# temperature-shift-r1.net
KiCad netlist of a schematic drawn in EAGLE
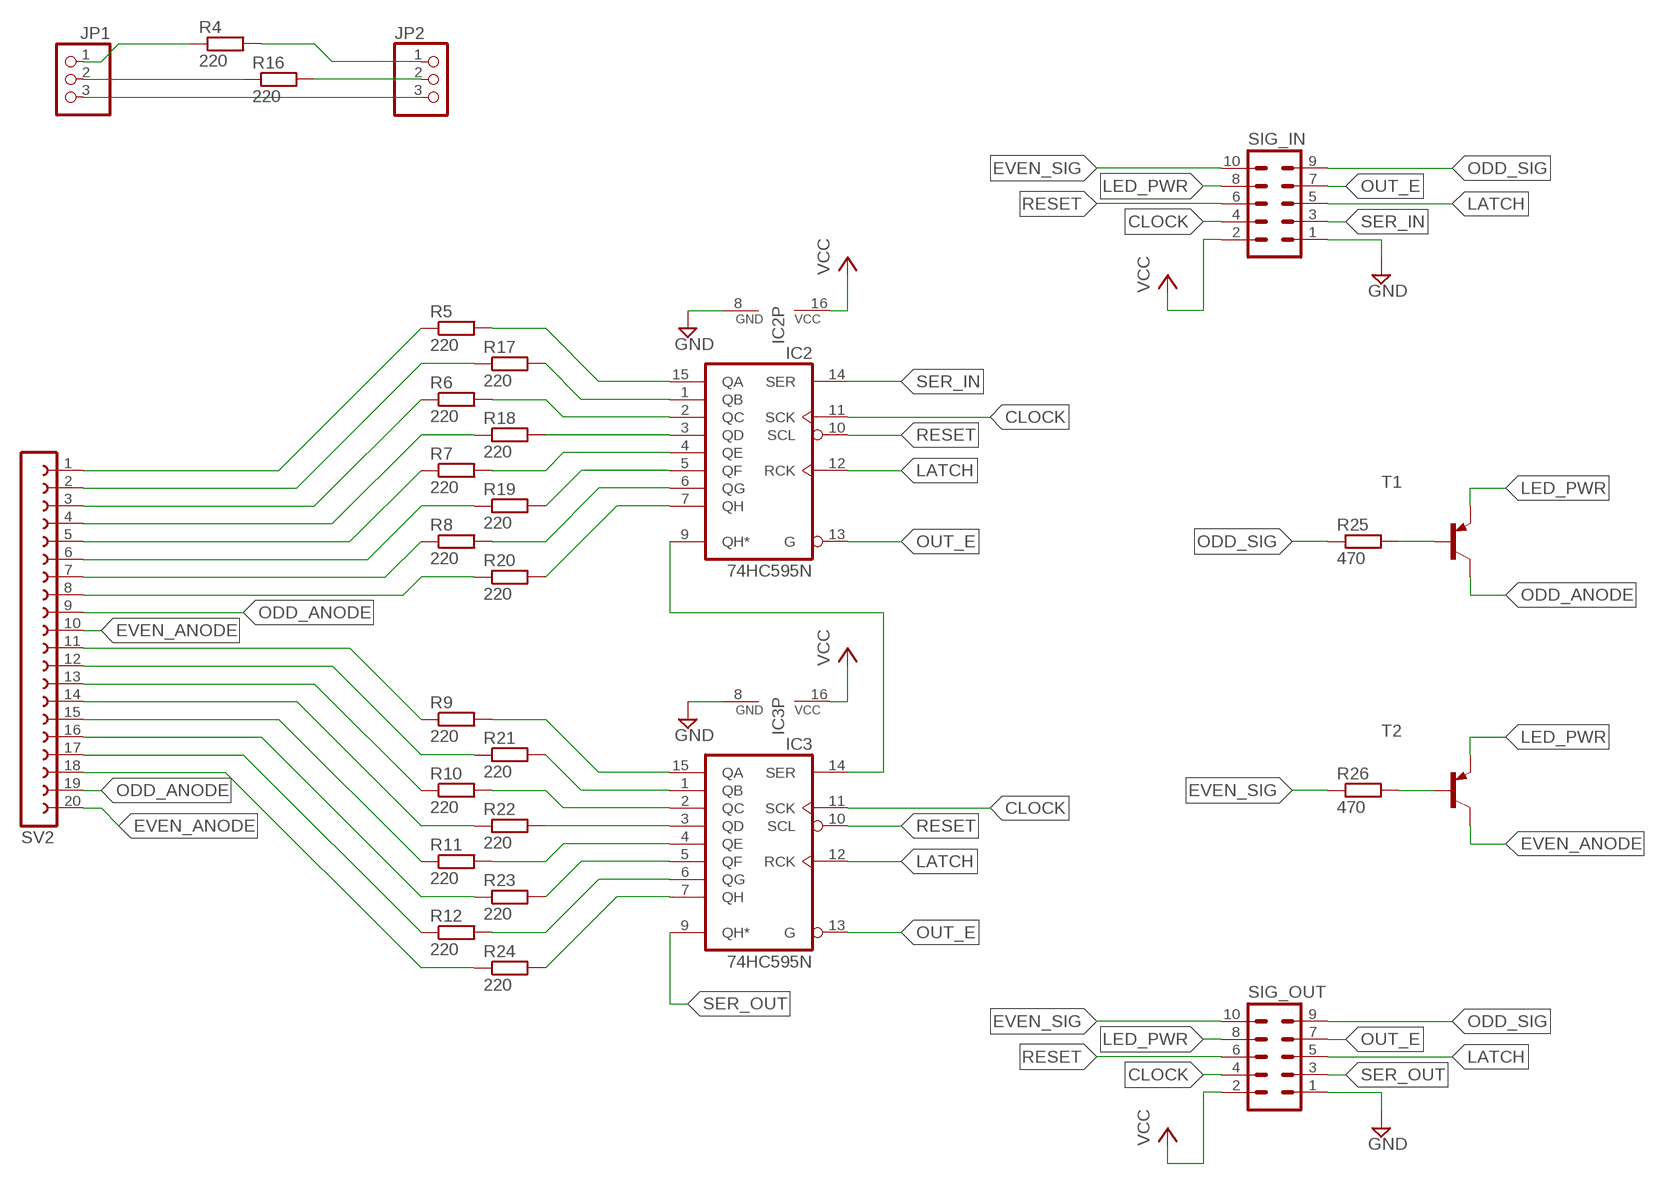
[diagram p0: schematic, sheet 1]

(export (version "E")
  (design (tool "Eeschema 10.0.6"))
  (components
    (comp (ref "IC2")
      (value "74HC595N")
      (footprint "eagle-import:DIL16")
      (libsource (lib "eagle-import") (part "74595NHC"))
    )
    (comp (ref "IC3")
      (value "74HC595N")
      (footprint "eagle-import:DIL16")
      (libsource (lib "eagle-import") (part "74595NHC"))
    )
    (comp (ref "JP1")
      (value "PINHD-1X3")
      (footprint "eagle-import:1X03")
      (libsource (lib "eagle-import") (part "PINHD-1X3"))
    )
    (comp (ref "JP2")
      (value "PINHD-1X3")
      (footprint "eagle-import:1X03")
      (libsource (lib "eagle-import") (part "PINHD-1X3"))
    )
    (comp (ref "R4")
      (value "220")
      (footprint "eagle-import:R0805")
      (libsource (lib "eagle-import") (part "R-EU_R0805"))
    )
    (comp (ref "R5")
      (value "220")
      (footprint "eagle-import:R0805")
      (libsource (lib "eagle-import") (part "R-EU_R0805"))
    )
    (comp (ref "R6")
      (value "220")
      (footprint "eagle-import:R0805")
      (libsource (lib "eagle-import") (part "R-EU_R0805"))
    )
    (comp (ref "R7")
      (value "220")
      (footprint "eagle-import:R0805")
      (libsource (lib "eagle-import") (part "R-EU_R0805"))
    )
    (comp (ref "R8")
      (value "220")
      (footprint "eagle-import:R0805")
      (libsource (lib "eagle-import") (part "R-EU_R0805"))
    )
    (comp (ref "R9")
      (value "220")
      (footprint "eagle-import:R0805")
      (libsource (lib "eagle-import") (part "R-EU_R0805"))
    )
    (comp (ref "R10")
      (value "220")
      (footprint "eagle-import:R0805")
      (libsource (lib "eagle-import") (part "R-EU_R0805"))
    )
    (comp (ref "R11")
      (value "220")
      (footprint "eagle-import:R0805")
      (libsource (lib "eagle-import") (part "R-EU_R0805"))
    )
    (comp (ref "R12")
      (value "220")
      (footprint "eagle-import:R0805")
      (libsource (lib "eagle-import") (part "R-EU_R0805"))
    )
    (comp (ref "R16")
      (value "220")
      (footprint "eagle-import:R0805")
      (libsource (lib "eagle-import") (part "R-EU_R0805"))
    )
    (comp (ref "R17")
      (value "220")
      (footprint "eagle-import:R0805")
      (libsource (lib "eagle-import") (part "R-EU_R0805"))
    )
    (comp (ref "R18")
      (value "220")
      (footprint "eagle-import:R0805")
      (libsource (lib "eagle-import") (part "R-EU_R0805"))
    )
    (comp (ref "R19")
      (value "220")
      (footprint "eagle-import:R0805")
      (libsource (lib "eagle-import") (part "R-EU_R0805"))
    )
    (comp (ref "R20")
      (value "220")
      (footprint "eagle-import:R0805")
      (libsource (lib "eagle-import") (part "R-EU_R0805"))
    )
    (comp (ref "R21")
      (value "220")
      (footprint "eagle-import:R0805")
      (libsource (lib "eagle-import") (part "R-EU_R0805"))
    )
    (comp (ref "R22")
      (value "220")
      (footprint "eagle-import:R0805")
      (libsource (lib "eagle-import") (part "R-EU_R0805"))
    )
    (comp (ref "R23")
      (value "220")
      (footprint "eagle-import:R0805")
      (libsource (lib "eagle-import") (part "R-EU_R0805"))
    )
    (comp (ref "R24")
      (value "220")
      (footprint "eagle-import:R0805")
      (libsource (lib "eagle-import") (part "R-EU_R0805"))
    )
    (comp (ref "R25")
      (value "470")
      (footprint "eagle-import:R0805")
      (libsource (lib "eagle-import") (part "R-EU_R0805"))
    )
    (comp (ref "R26")
      (value "470")
      (footprint "eagle-import:R0805")
      (libsource (lib "eagle-import") (part "R-EU_R0805"))
    )
    (comp (ref "SIG_IN")
      (value "MA05-2")
      (footprint "eagle-import:MA05-2")
      (libsource (lib "eagle-import") (part "MA05-2"))
    )
    (comp (ref "SIG_OUT")
      (value "MA05-2")
      (footprint "eagle-import:MA05-2")
      (libsource (lib "eagle-import") (part "MA05-2"))
    )
    (comp (ref "SV2")
      (value "FE20-1")
      (footprint "eagle-import:FE20")
      (libsource (lib "eagle-import") (part "FE20-1"))
    )
    (comp (ref "T1")
      (value "BC557B-PNP-TO92-EBC")
      (footprint "eagle-import:TO92-EBC")
      (libsource (lib "eagle-import") (part "-PNP-TO92-EBCBC557B"))
    )
    (comp (ref "T2")
      (value "BC557B-PNP-TO92-EBC")
      (footprint "eagle-import:TO92-EBC")
      (libsource (lib "eagle-import") (part "-PNP-TO92-EBCBC557B"))
    )
  )
  (nets
    (net (code "1") (name "CLOCK") (class "Default")
      (node (ref "IC2") (pin "11") (pinfunction "SCK_11") (pintype "input"))
      (node (ref "IC3") (pin "11") (pinfunction "SCK_11") (pintype "input"))
      (node (ref "SIG_IN") (pin "4") (pinfunction "4_4") (pintype "passive"))
      (node (ref "SIG_OUT") (pin "4") (pinfunction "4_4") (pintype "passive"))
    )
    (net (code "2") (name "EVEN_ANODE") (class "Default")
      (node (ref "SV2") (pin "10") (pinfunction "10_10") (pintype "passive"))
      (node (ref "SV2") (pin "20") (pinfunction "20_20") (pintype "passive"))
      (node (ref "T2") (pin "C") (pinfunction "C_C") (pintype "passive"))
    )
    (net (code "3") (name "EVEN_SIG") (class "Default")
      (node (ref "R26") (pin "1") (pinfunction "1_1") (pintype "passive"))
      (node (ref "SIG_IN") (pin "10") (pinfunction "10_10") (pintype "passive"))
      (node (ref "SIG_OUT") (pin "10") (pinfunction "10_10") (pintype "passive"))
    )
    (net (code "4") (name "GND") (class "Default")
      (node (ref "IC2") (pin "8") (pinfunction "GND_8") (pintype "power_in"))
      (node (ref "IC3") (pin "8") (pinfunction "GND_8") (pintype "power_in"))
      (node (ref "SIG_IN") (pin "1") (pinfunction "1_1") (pintype "passive"))
      (node (ref "SIG_OUT") (pin "1") (pinfunction "1_1") (pintype "passive"))
    )
    (net (code "5") (name "LATCH") (class "Default")
      (node (ref "IC2") (pin "12") (pinfunction "RCK_12") (pintype "input"))
      (node (ref "IC3") (pin "12") (pinfunction "RCK_12") (pintype "input"))
      (node (ref "SIG_IN") (pin "5") (pinfunction "5_5") (pintype "passive"))
      (node (ref "SIG_OUT") (pin "5") (pinfunction "5_5") (pintype "passive"))
    )
    (net (code "6") (name "LED_PWR") (class "Default")
      (node (ref "SIG_IN") (pin "8") (pinfunction "8_8") (pintype "passive"))
      (node (ref "SIG_OUT") (pin "8") (pinfunction "8_8") (pintype "passive"))
      (node (ref "T1") (pin "E") (pinfunction "E_E") (pintype "passive"))
      (node (ref "T2") (pin "E") (pinfunction "E_E") (pintype "passive"))
    )
    (net (code "7") (name "Net-(IC2A-QA)") (class "Default")
      (node (ref "IC2") (pin "15") (pinfunction "QA_15") (pintype "tri_state"))
      (node (ref "R5") (pin "2") (pinfunction "2_2") (pintype "passive"))
    )
    (net (code "8") (name "Net-(IC2A-QB)") (class "Default")
      (node (ref "IC2") (pin "1") (pinfunction "QB_1") (pintype "tri_state"))
      (node (ref "R17") (pin "2") (pinfunction "2_2") (pintype "passive"))
    )
    (net (code "9") (name "Net-(IC2A-QC)") (class "Default")
      (node (ref "IC2") (pin "2") (pinfunction "QC_2") (pintype "tri_state"))
      (node (ref "R6") (pin "2") (pinfunction "2_2") (pintype "passive"))
    )
    (net (code "10") (name "Net-(IC2A-QD)") (class "Default")
      (node (ref "IC2") (pin "3") (pinfunction "QD_3") (pintype "tri_state"))
      (node (ref "R18") (pin "2") (pinfunction "2_2") (pintype "passive"))
    )
    (net (code "11") (name "Net-(IC2A-QE)") (class "Default")
      (node (ref "IC2") (pin "4") (pinfunction "QE_4") (pintype "tri_state"))
      (node (ref "R7") (pin "2") (pinfunction "2_2") (pintype "passive"))
    )
    (net (code "12") (name "Net-(IC2A-QF)") (class "Default")
      (node (ref "IC2") (pin "5") (pinfunction "QF_5") (pintype "tri_state"))
      (node (ref "R19") (pin "2") (pinfunction "2_2") (pintype "passive"))
    )
    (net (code "13") (name "Net-(IC2A-QG)") (class "Default")
      (node (ref "IC2") (pin "6") (pinfunction "QG_6") (pintype "tri_state"))
      (node (ref "R8") (pin "2") (pinfunction "2_2") (pintype "passive"))
    )
    (net (code "14") (name "Net-(IC2A-QH)") (class "Default")
      (node (ref "IC2") (pin "7") (pinfunction "QH_7") (pintype "tri_state"))
      (node (ref "R20") (pin "2") (pinfunction "2_2") (pintype "passive"))
    )
    (net (code "15") (name "Net-(IC2A-QH*)") (class "Default")
      (node (ref "IC2") (pin "9") (pinfunction "QH*_9") (pintype "tri_state"))
      (node (ref "IC3") (pin "14") (pinfunction "SER_14") (pintype "input"))
    )
    (net (code "16") (name "Net-(IC3A-QA)") (class "Default")
      (node (ref "IC3") (pin "15") (pinfunction "QA_15") (pintype "tri_state"))
      (node (ref "R9") (pin "2") (pinfunction "2_2") (pintype "passive"))
    )
    (net (code "17") (name "Net-(IC3A-QB)") (class "Default")
      (node (ref "IC3") (pin "1") (pinfunction "QB_1") (pintype "tri_state"))
      (node (ref "R21") (pin "2") (pinfunction "2_2") (pintype "passive"))
    )
    (net (code "18") (name "Net-(IC3A-QC)") (class "Default")
      (node (ref "IC3") (pin "2") (pinfunction "QC_2") (pintype "tri_state"))
      (node (ref "R10") (pin "2") (pinfunction "2_2") (pintype "passive"))
    )
    (net (code "19") (name "Net-(IC3A-QD)") (class "Default")
      (node (ref "IC3") (pin "3") (pinfunction "QD_3") (pintype "tri_state"))
      (node (ref "R22") (pin "2") (pinfunction "2_2") (pintype "passive"))
    )
    (net (code "20") (name "Net-(IC3A-QE)") (class "Default")
      (node (ref "IC3") (pin "4") (pinfunction "QE_4") (pintype "tri_state"))
      (node (ref "R11") (pin "2") (pinfunction "2_2") (pintype "passive"))
    )
    (net (code "21") (name "Net-(IC3A-QF)") (class "Default")
      (node (ref "IC3") (pin "5") (pinfunction "QF_5") (pintype "tri_state"))
      (node (ref "R23") (pin "2") (pinfunction "2_2") (pintype "passive"))
    )
    (net (code "22") (name "Net-(IC3A-QG)") (class "Default")
      (node (ref "IC3") (pin "6") (pinfunction "QG_6") (pintype "tri_state"))
      (node (ref "R12") (pin "2") (pinfunction "2_2") (pintype "passive"))
    )
    (net (code "23") (name "Net-(IC3A-QH)") (class "Default")
      (node (ref "IC3") (pin "7") (pinfunction "QH_7") (pintype "tri_state"))
      (node (ref "R24") (pin "2") (pinfunction "2_2") (pintype "passive"))
    )
    (net (code "24") (name "Net-(JP1-Pad1)") (class "Default")
      (node (ref "JP1") (pin "1") (pinfunction "1_1") (pintype "passive"))
      (node (ref "R4") (pin "1") (pinfunction "1_1") (pintype "passive"))
    )
    (net (code "25") (name "Net-(JP1-Pad2)") (class "Default")
      (node (ref "JP1") (pin "2") (pinfunction "2_2") (pintype "passive"))
      (node (ref "R16") (pin "1") (pinfunction "1_1") (pintype "passive"))
    )
    (net (code "26") (name "Net-(JP1-Pad3)") (class "Default")
      (node (ref "JP1") (pin "3") (pinfunction "3_3") (pintype "passive"))
      (node (ref "JP2") (pin "3") (pinfunction "3_3") (pintype "passive"))
    )
    (net (code "27") (name "Net-(JP2-Pad1)") (class "Default")
      (node (ref "JP2") (pin "1") (pinfunction "1_1") (pintype "passive"))
      (node (ref "R4") (pin "2") (pinfunction "2_2") (pintype "passive"))
    )
    (net (code "28") (name "Net-(JP2-Pad2)") (class "Default")
      (node (ref "JP2") (pin "2") (pinfunction "2_2") (pintype "passive"))
      (node (ref "R16") (pin "2") (pinfunction "2_2") (pintype "passive"))
    )
    (net (code "29") (name "Net-(R5-Pad1)") (class "Default")
      (node (ref "R5") (pin "1") (pinfunction "1_1") (pintype "passive"))
      (node (ref "SV2") (pin "1") (pinfunction "1_1") (pintype "passive"))
    )
    (net (code "30") (name "Net-(R6-Pad1)") (class "Default")
      (node (ref "R6") (pin "1") (pinfunction "1_1") (pintype "passive"))
      (node (ref "SV2") (pin "3") (pinfunction "3_3") (pintype "passive"))
    )
    (net (code "31") (name "Net-(R7-Pad1)") (class "Default")
      (node (ref "R7") (pin "1") (pinfunction "1_1") (pintype "passive"))
      (node (ref "SV2") (pin "5") (pinfunction "5_5") (pintype "passive"))
    )
    (net (code "32") (name "Net-(R8-Pad1)") (class "Default")
      (node (ref "R8") (pin "1") (pinfunction "1_1") (pintype "passive"))
      (node (ref "SV2") (pin "7") (pinfunction "7_7") (pintype "passive"))
    )
    (net (code "33") (name "Net-(R9-Pad1)") (class "Default")
      (node (ref "R9") (pin "1") (pinfunction "1_1") (pintype "passive"))
      (node (ref "SV2") (pin "11") (pinfunction "11_11") (pintype "passive"))
    )
    (net (code "34") (name "Net-(R10-Pad1)") (class "Default")
      (node (ref "R10") (pin "1") (pinfunction "1_1") (pintype "passive"))
      (node (ref "SV2") (pin "13") (pinfunction "13_13") (pintype "passive"))
    )
    (net (code "35") (name "Net-(R11-Pad1)") (class "Default")
      (node (ref "R11") (pin "1") (pinfunction "1_1") (pintype "passive"))
      (node (ref "SV2") (pin "15") (pinfunction "15_15") (pintype "passive"))
    )
    (net (code "36") (name "Net-(R12-Pad1)") (class "Default")
      (node (ref "R12") (pin "1") (pinfunction "1_1") (pintype "passive"))
      (node (ref "SV2") (pin "17") (pinfunction "17_17") (pintype "passive"))
    )
    (net (code "37") (name "Net-(R17-Pad1)") (class "Default")
      (node (ref "R17") (pin "1") (pinfunction "1_1") (pintype "passive"))
      (node (ref "SV2") (pin "2") (pinfunction "2_2") (pintype "passive"))
    )
    (net (code "38") (name "Net-(R18-Pad1)") (class "Default")
      (node (ref "R18") (pin "1") (pinfunction "1_1") (pintype "passive"))
      (node (ref "SV2") (pin "4") (pinfunction "4_4") (pintype "passive"))
    )
    (net (code "39") (name "Net-(R19-Pad1)") (class "Default")
      (node (ref "R19") (pin "1") (pinfunction "1_1") (pintype "passive"))
      (node (ref "SV2") (pin "6") (pinfunction "6_6") (pintype "passive"))
    )
    (net (code "40") (name "Net-(R20-Pad1)") (class "Default")
      (node (ref "R20") (pin "1") (pinfunction "1_1") (pintype "passive"))
      (node (ref "SV2") (pin "8") (pinfunction "8_8") (pintype "passive"))
    )
    (net (code "41") (name "Net-(R21-Pad1)") (class "Default")
      (node (ref "R21") (pin "1") (pinfunction "1_1") (pintype "passive"))
      (node (ref "SV2") (pin "12") (pinfunction "12_12") (pintype "passive"))
    )
    (net (code "42") (name "Net-(R22-Pad1)") (class "Default")
      (node (ref "R22") (pin "1") (pinfunction "1_1") (pintype "passive"))
      (node (ref "SV2") (pin "14") (pinfunction "14_14") (pintype "passive"))
    )
    (net (code "43") (name "Net-(R23-Pad1)") (class "Default")
      (node (ref "R23") (pin "1") (pinfunction "1_1") (pintype "passive"))
      (node (ref "SV2") (pin "16") (pinfunction "16_16") (pintype "passive"))
    )
    (net (code "44") (name "Net-(R24-Pad1)") (class "Default")
      (node (ref "R24") (pin "1") (pinfunction "1_1") (pintype "passive"))
      (node (ref "SV2") (pin "18") (pinfunction "18_18") (pintype "passive"))
    )
    (net (code "45") (name "Net-(R25-Pad2)") (class "Default")
      (node (ref "R25") (pin "2") (pinfunction "2_2") (pintype "passive"))
      (node (ref "T1") (pin "B") (pinfunction "B_B") (pintype "passive"))
    )
    (net (code "46") (name "Net-(R26-Pad2)") (class "Default")
      (node (ref "R26") (pin "2") (pinfunction "2_2") (pintype "passive"))
      (node (ref "T2") (pin "B") (pinfunction "B_B") (pintype "passive"))
    )
    (net (code "47") (name "ODD_ANODE") (class "Default")
      (node (ref "SV2") (pin "19") (pinfunction "19_19") (pintype "passive"))
      (node (ref "SV2") (pin "9") (pinfunction "9_9") (pintype "passive"))
      (node (ref "T1") (pin "C") (pinfunction "C_C") (pintype "passive"))
    )
    (net (code "48") (name "ODD_SIG") (class "Default")
      (node (ref "R25") (pin "1") (pinfunction "1_1") (pintype "passive"))
      (node (ref "SIG_IN") (pin "9") (pinfunction "9_9") (pintype "passive"))
      (node (ref "SIG_OUT") (pin "9") (pinfunction "9_9") (pintype "passive"))
    )
    (net (code "49") (name "OUT_E") (class "Default")
      (node (ref "IC2") (pin "13") (pinfunction "G_13") (pintype "input"))
      (node (ref "IC3") (pin "13") (pinfunction "G_13") (pintype "input"))
      (node (ref "SIG_IN") (pin "7") (pinfunction "7_7") (pintype "passive"))
      (node (ref "SIG_OUT") (pin "7") (pinfunction "7_7") (pintype "passive"))
    )
    (net (code "50") (name "RESET") (class "Default")
      (node (ref "IC2") (pin "10") (pinfunction "SCL_10") (pintype "input"))
      (node (ref "IC3") (pin "10") (pinfunction "SCL_10") (pintype "input"))
      (node (ref "SIG_IN") (pin "6") (pinfunction "6_6") (pintype "passive"))
      (node (ref "SIG_OUT") (pin "6") (pinfunction "6_6") (pintype "passive"))
    )
    (net (code "51") (name "SER_IN") (class "Default")
      (node (ref "IC2") (pin "14") (pinfunction "SER_14") (pintype "input"))
      (node (ref "SIG_IN") (pin "3") (pinfunction "3_3") (pintype "passive"))
    )
    (net (code "52") (name "SER_OUT") (class "Default")
      (node (ref "IC3") (pin "9") (pinfunction "QH*_9") (pintype "tri_state"))
      (node (ref "SIG_OUT") (pin "3") (pinfunction "3_3") (pintype "passive"))
    )
    (net (code "53") (name "VCC") (class "Default")
      (node (ref "IC2") (pin "16") (pinfunction "VCC_16") (pintype "power_in"))
      (node (ref "IC3") (pin "16") (pinfunction "VCC_16") (pintype "power_in"))
      (node (ref "SIG_IN") (pin "2") (pinfunction "2_2") (pintype "passive"))
      (node (ref "SIG_OUT") (pin "2") (pinfunction "2_2") (pintype "passive"))
    )
  )
)
